# mk-logic-bt.net
KiCad netlist of a schematic drawn in EAGLE
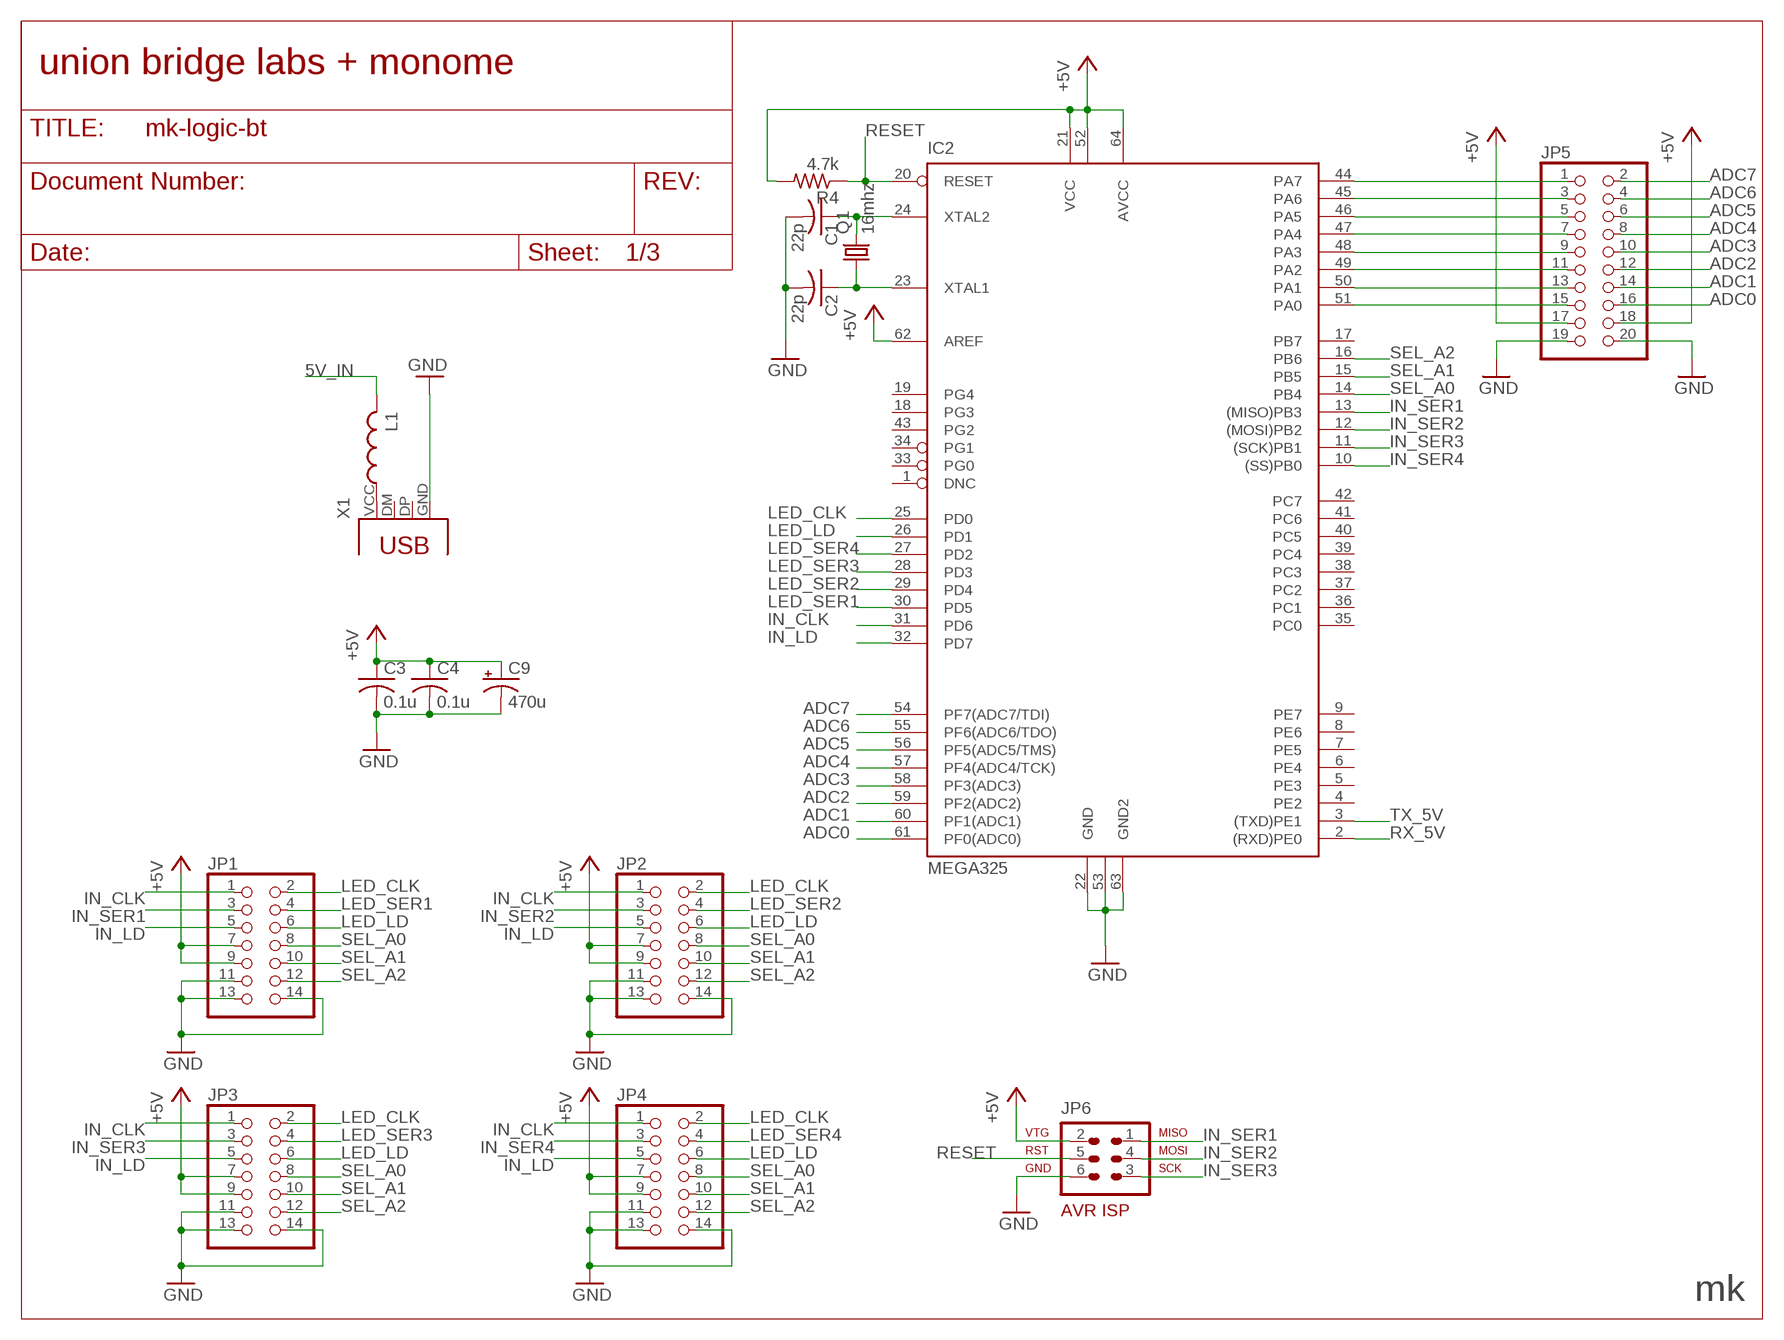
[diagram p0: schematic, sheet 1]
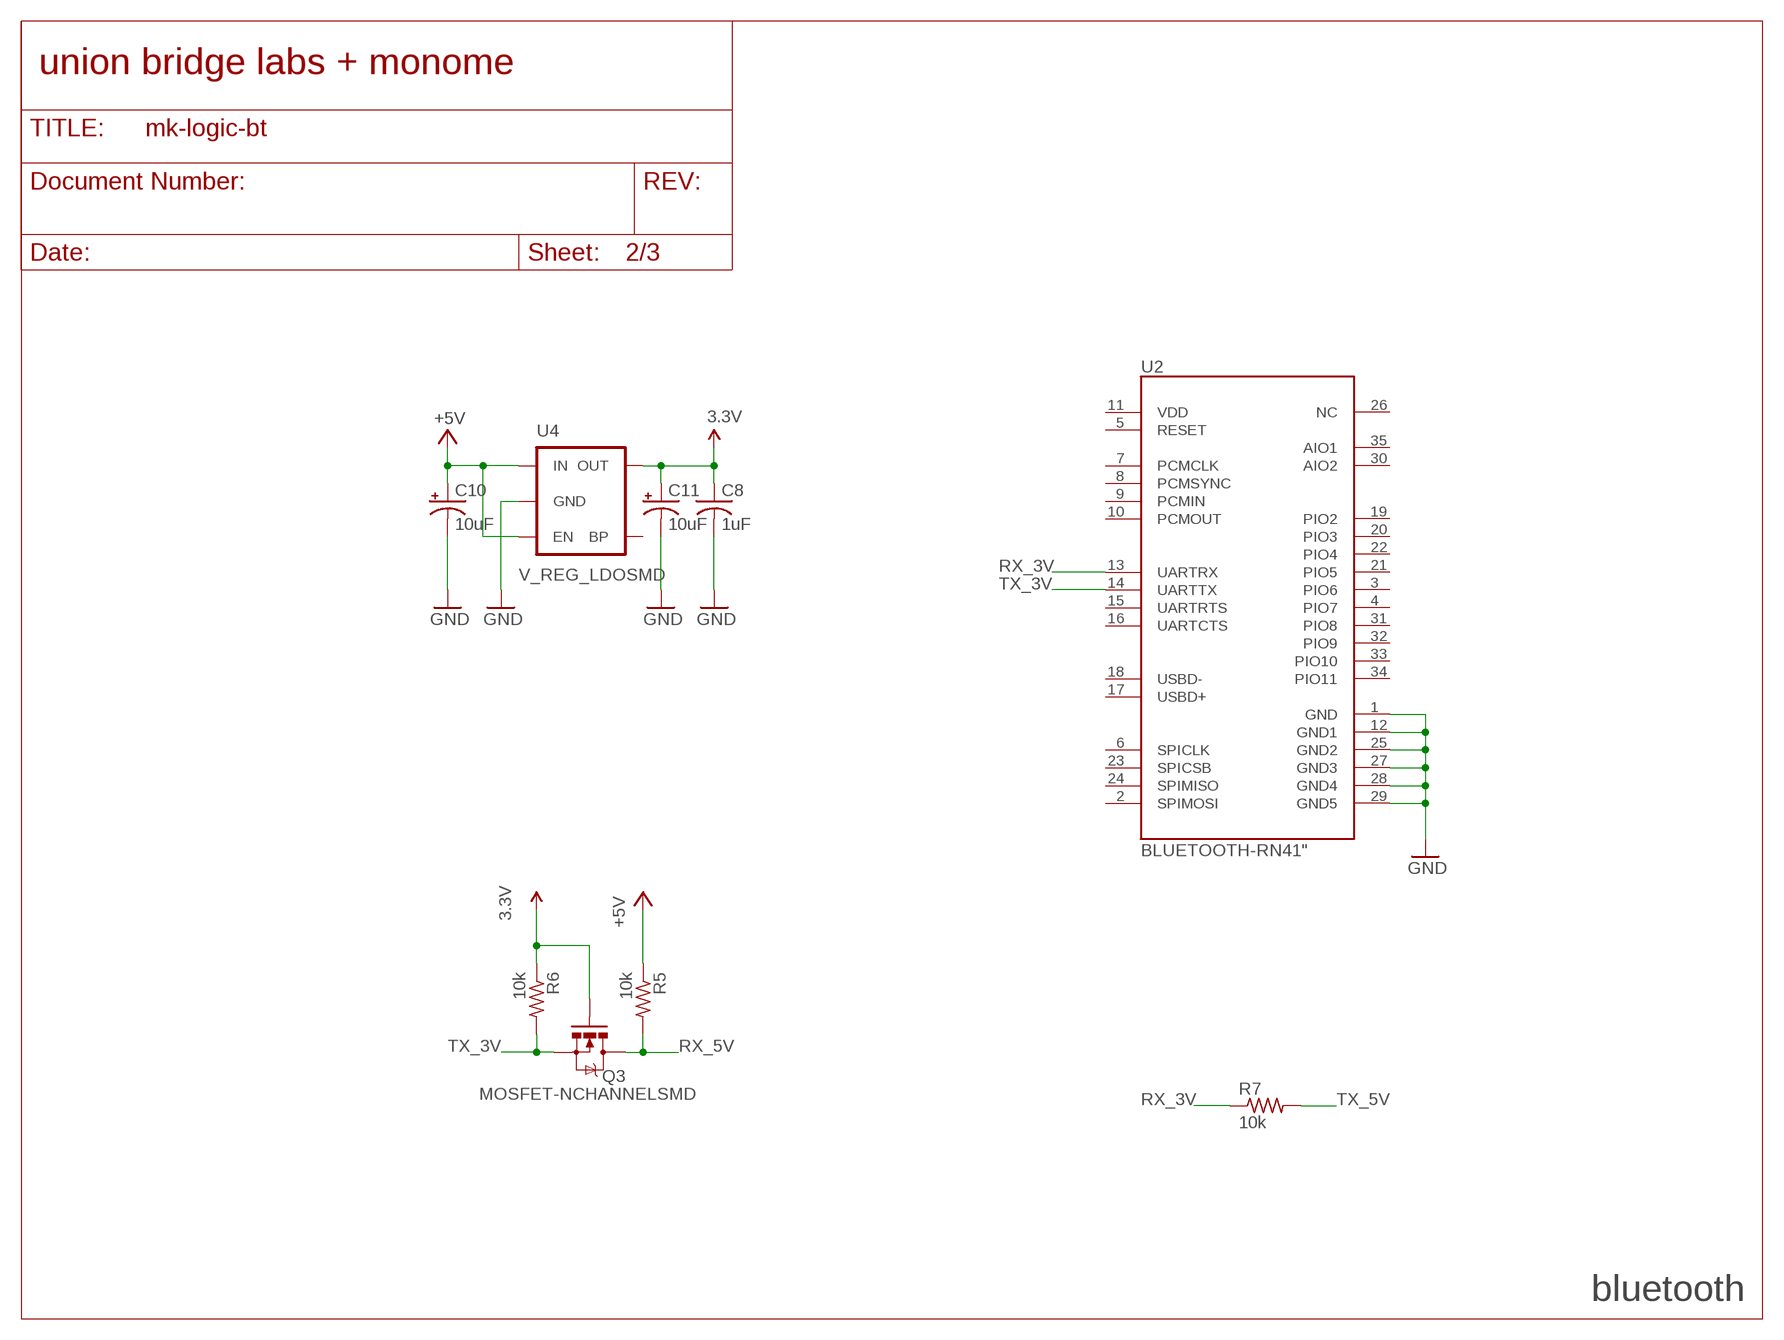
[diagram p1: schematic, sheet 2]
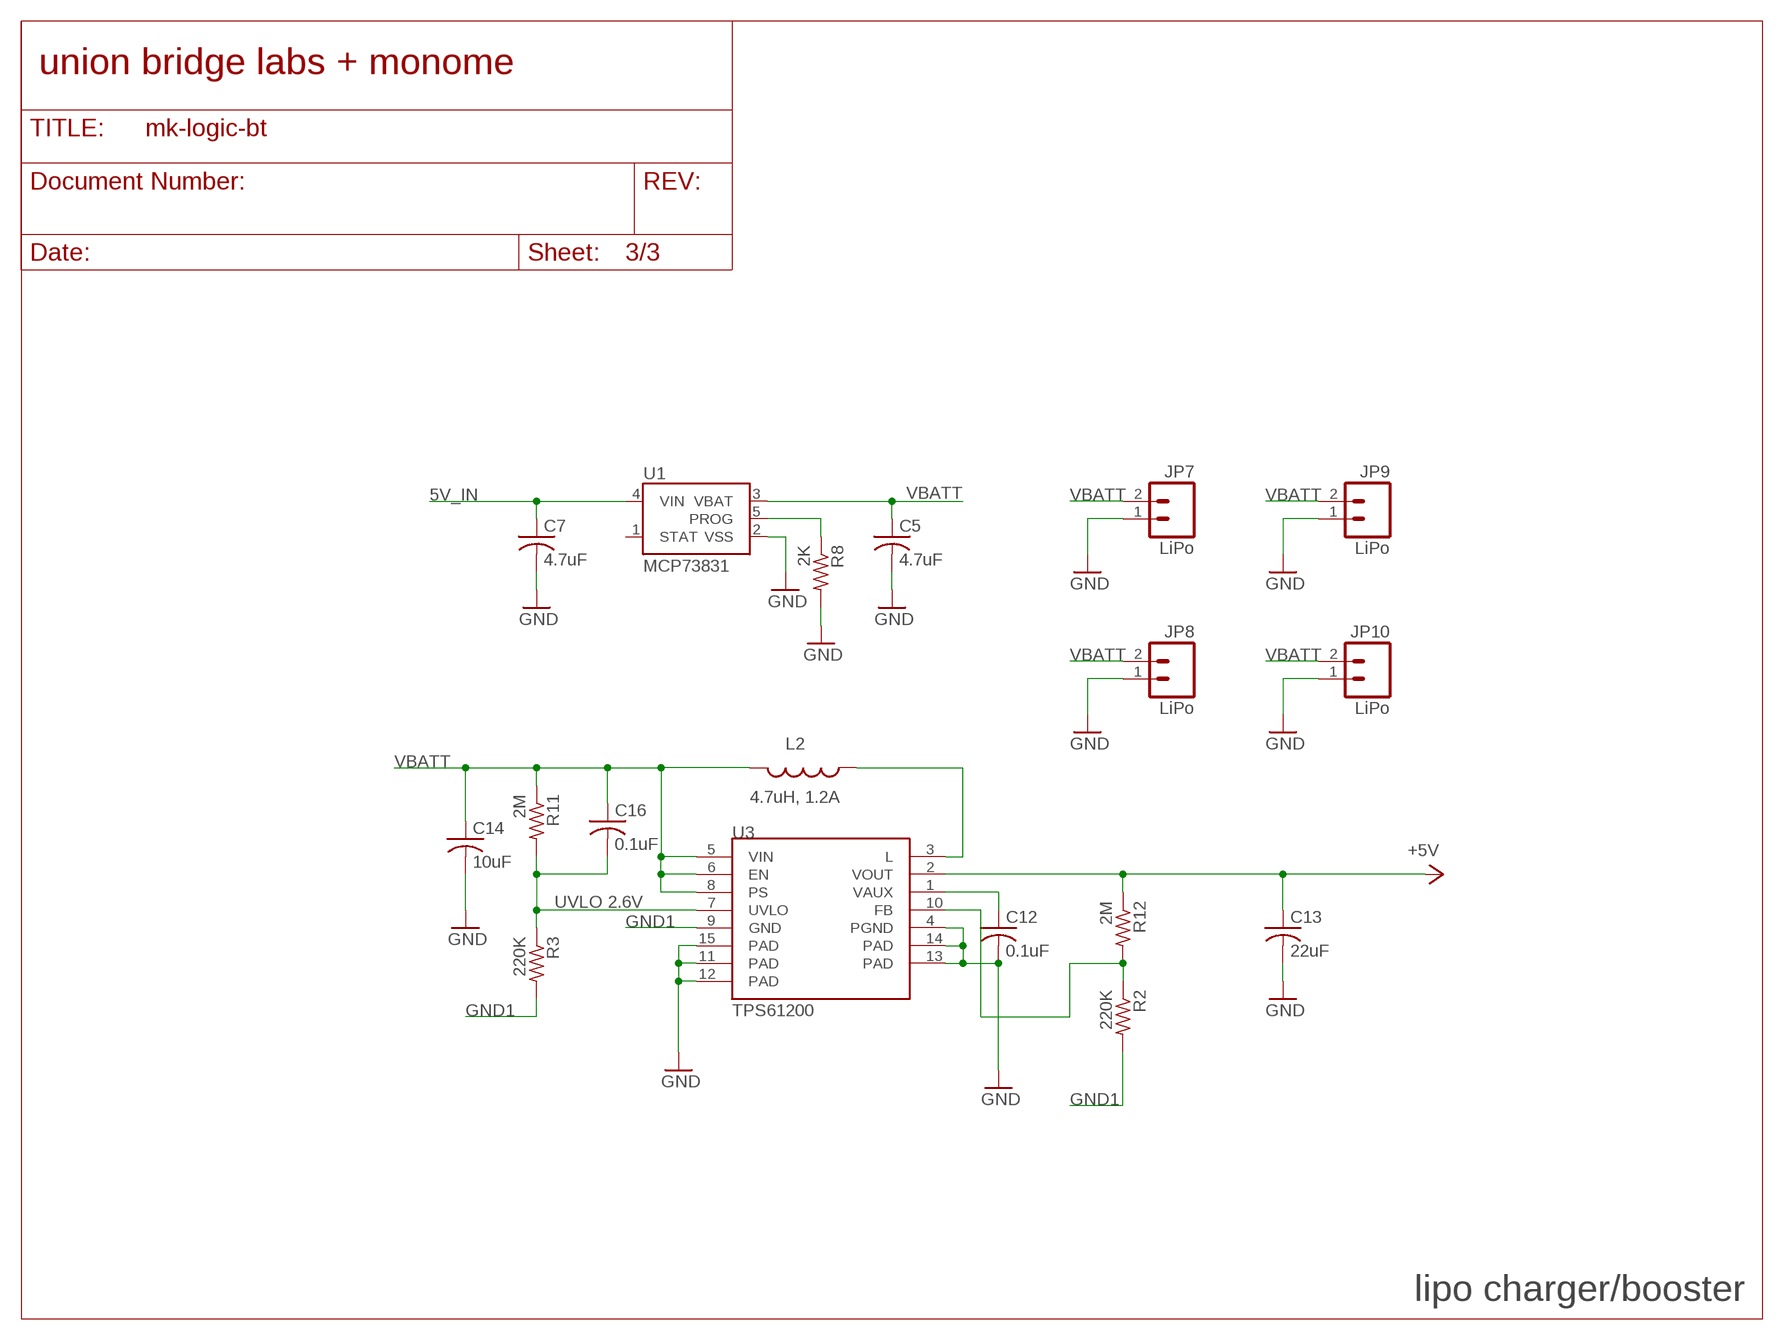
[diagram p2: schematic, sheet 3]

(export (version "E")
  (design (tool "Eeschema 10.0.6"))
  (components
    (comp (ref "C1")
      (value "22p")
      (footprint "eagle-import:C1206")
      (libsource (lib "eagle-import") (part "C-USC1206"))
    )
    (comp (ref "C2")
      (value "22p")
      (footprint "eagle-import:C1206")
      (libsource (lib "eagle-import") (part "C-USC1206"))
    )
    (comp (ref "C3")
      (value "0.1u")
      (footprint "eagle-import:C1206")
      (libsource (lib "eagle-import") (part "C-USC1206"))
    )
    (comp (ref "C4")
      (value "0.1u")
      (footprint "eagle-import:C1206")
      (libsource (lib "eagle-import") (part "C-USC1206"))
    )
    (comp (ref "C9")
      (value "470u")
      (footprint "eagle-import:PANASONIC_E")
      (libsource (lib "eagle-import") (part "CPOL-USE"))
    )
    (comp (ref "IC2")
      (value "MEGA325")
      (footprint "eagle-import:TQFP64")
      (libsource (lib "eagle-import") (part "MEGA325"))
    )
    (comp (ref "JP1")
      (value "PINHD-2X7")
      (footprint "eagle-import:2X07")
      (libsource (lib "eagle-import") (part "PINHD-2X7"))
    )
    (comp (ref "JP2")
      (value "PINHD-2X7")
      (footprint "eagle-import:2X07")
      (libsource (lib "eagle-import") (part "PINHD-2X7"))
    )
    (comp (ref "JP3")
      (value "PINHD-2X7")
      (footprint "eagle-import:2X07")
      (libsource (lib "eagle-import") (part "PINHD-2X7"))
    )
    (comp (ref "JP4")
      (value "PINHD-2X7")
      (footprint "eagle-import:2X07")
      (libsource (lib "eagle-import") (part "PINHD-2X7"))
    )
    (comp (ref "JP5")
      (value "PINHD-2X10")
      (footprint "eagle-import:2X10")
      (libsource (lib "eagle-import") (part "PINHD-2X10"))
    )
    (comp (ref "JP6")
      (value "AVR-ISP")
      (footprint "eagle-import:AVR-ISP-6")
      (libsource (lib "eagle-import") (part "AVR-ISP-6"))
    )
    (comp (ref "L1")
      (value "L-USL3216C")
      (footprint "eagle-import:L3216C")
      (libsource (lib "eagle-import") (part "L-USL3216C"))
    )
    (comp (ref "Q1")
      (value "16mhz")
      (footprint "eagle-import:HC49UP")
      (libsource (lib "eagle-import") (part "CRYTALHC49UP"))
    )
    (comp (ref "R4")
      (value "4.7k")
      (footprint "eagle-import:R1206")
      (libsource (lib "eagle-import") (part "R-US_R1206"))
    )
    (comp (ref "X1")
      (value "USB_TYPE_B")
      (footprint "eagle-import:USB_B")
      (libsource (lib "eagle-import") (part "USB_TYPE_B"))
    )
    (comp (ref "C5")
      (value "4.7uF")
      (footprint "eagle-import:C1206")
      (libsource (lib "eagle-import") (part "C-USC1206"))
    )
    (comp (ref "C7")
      (value "4.7uF")
      (footprint "eagle-import:C1206")
      (libsource (lib "eagle-import") (part "C-USC1206"))
    )
    (comp (ref "C12")
      (value "0.1uF")
      (footprint "eagle-import:C1206")
      (libsource (lib "eagle-import") (part "C-USC1206"))
    )
    (comp (ref "C13")
      (value "22uF")
      (footprint "eagle-import:C1206")
      (libsource (lib "eagle-import") (part "C-USC1206"))
    )
    (comp (ref "C14")
      (value "10uF")
      (footprint "eagle-import:C1206")
      (libsource (lib "eagle-import") (part "C-USC1206"))
    )
    (comp (ref "C16")
      (value "0.1uF")
      (footprint "eagle-import:C1206")
      (libsource (lib "eagle-import") (part "C-USC1206"))
    )
    (comp (ref "JP7")
      (value "LiPo")
      (footprint "eagle-import:JST-2-SMD")
      (libsource (lib "eagle-import") (part "M02-JST-2MM-SMT"))
    )
    (comp (ref "JP8")
      (value "LiPo")
      (footprint "eagle-import:JST-2-SMD")
      (libsource (lib "eagle-import") (part "M02-JST-2MM-SMT"))
    )
    (comp (ref "JP9")
      (value "LiPo")
      (footprint "eagle-import:JST-2-SMD")
      (libsource (lib "eagle-import") (part "M02-JST-2MM-SMT"))
    )
    (comp (ref "JP10")
      (value "LiPo")
      (footprint "eagle-import:JST-2-SMD")
      (libsource (lib "eagle-import") (part "M02-JST-2MM-SMT"))
    )
    (comp (ref "L2")
      (value "4.7uH, 1.2A")
      (footprint "eagle-import:CDRH2D09")
      (libsource (lib "eagle-import") (part "INDUCTOR."))
    )
    (comp (ref "R2")
      (value "220K")
      (footprint "eagle-import:R1206")
      (libsource (lib "eagle-import") (part "R-US_R1206"))
    )
    (comp (ref "R3")
      (value "220K")
      (footprint "eagle-import:R1206")
      (libsource (lib "eagle-import") (part "R-US_R1206"))
    )
    (comp (ref "R8")
      (value "2K")
      (footprint "eagle-import:R1206")
      (libsource (lib "eagle-import") (part "R-US_R1206"))
    )
    (comp (ref "R11")
      (value "2M")
      (footprint "eagle-import:R1206")
      (libsource (lib "eagle-import") (part "R-US_R1206"))
    )
    (comp (ref "R12")
      (value "2M")
      (footprint "eagle-import:R1206")
      (libsource (lib "eagle-import") (part "R-US_R1206"))
    )
    (comp (ref "U1")
      (value "MCP73831")
      (footprint "eagle-import:SOT23-5")
      (libsource (lib "eagle-import") (part "MCP73831"))
    )
    (comp (ref "U3")
      (value "TPS61200")
      (footprint "eagle-import:QFN-10_PAD")
      (libsource (lib "eagle-import") (part "TPS61200"))
    )
    (comp (ref "C8")
      (value "1uF")
      (footprint "eagle-import:C1206")
      (libsource (lib "eagle-import") (part "C-USC1206"))
    )
    (comp (ref "C10")
      (value "10uF")
      (footprint "eagle-import:EIA3216")
      (libsource (lib "eagle-import") (part "CAP_POL1206"))
    )
    (comp (ref "C11")
      (value "10uF")
      (footprint "eagle-import:EIA3216")
      (libsource (lib "eagle-import") (part "CAP_POL1206"))
    )
    (comp (ref "Q3")
      (value "MOSFET-NCHANNELSMD")
      (footprint "eagle-import:SOT23-3")
      (libsource (lib "eagle-import") (part "MOSFET-NCHANNELSMD"))
    )
    (comp (ref "R5")
      (value "10k")
      (footprint "eagle-import:R1206")
      (libsource (lib "eagle-import") (part "R-US_R1206"))
    )
    (comp (ref "R6")
      (value "10k")
      (footprint "eagle-import:R1206")
      (libsource (lib "eagle-import") (part "R-US_R1206"))
    )
    (comp (ref "R7")
      (value "10k")
      (footprint "eagle-import:R1206")
      (libsource (lib "eagle-import") (part "R-US_R1206"))
    )
    (comp (ref "U2")
      (value "BLUETOOTH-RN41\"")
      (footprint "eagle-import:RN41")
      (libsource (lib "eagle-import") (part "BLUETOOTH-RN41{dblquote}"))
    )
    (comp (ref "U4")
      (value "V_REG_LDOSMD")
      (footprint "eagle-import:SOT23-5")
      (libsource (lib "eagle-import") (part "V_REG_LDOSMD"))
    )
  )
  (nets
    (net (code "1") (name "+5V") (class "Default")
      (node (ref "C10") (pin "A") (pinfunction "+_A") (pintype "passive"))
      (node (ref "C13") (pin "1") (pinfunction "1_1") (pintype "passive"))
      (node (ref "C3") (pin "1") (pinfunction "1_1") (pintype "passive"))
      (node (ref "C4") (pin "1") (pinfunction "1_1") (pintype "passive"))
      (node (ref "C9") (pin "+") (pinfunction "+_+") (pintype "passive"))
      (node (ref "IC2") (pin "21") (pinfunction "VCC_21") (pintype "power_in"))
      (node (ref "IC2") (pin "52") (pinfunction "VCC1_52") (pintype "power_in"))
      (node (ref "IC2") (pin "62") (pinfunction "AREF_62") (pintype "bidirectional"))
      (node (ref "IC2") (pin "64") (pinfunction "AVCC_64") (pintype "bidirectional"))
      (node (ref "JP1") (pin "7") (pinfunction "7_7") (pintype "passive"))
      (node (ref "JP1") (pin "9") (pinfunction "9_9") (pintype "passive"))
      (node (ref "JP2") (pin "7") (pinfunction "7_7") (pintype "passive"))
      (node (ref "JP2") (pin "9") (pinfunction "9_9") (pintype "passive"))
      (node (ref "JP3") (pin "7") (pinfunction "7_7") (pintype "passive"))
      (node (ref "JP3") (pin "9") (pinfunction "9_9") (pintype "passive"))
      (node (ref "JP4") (pin "7") (pinfunction "7_7") (pintype "passive"))
      (node (ref "JP4") (pin "9") (pinfunction "9_9") (pintype "passive"))
      (node (ref "JP5") (pin "17") (pinfunction "17_17") (pintype "passive"))
      (node (ref "JP5") (pin "18") (pinfunction "18_18") (pintype "passive"))
      (node (ref "JP6") (pin "2") (pinfunction "2_2") (pintype "passive"))
      (node (ref "R12") (pin "1") (pinfunction "1_1") (pintype "passive"))
      (node (ref "R4") (pin "2") (pinfunction "2_2") (pintype "passive"))
      (node (ref "R5") (pin "1") (pinfunction "1_1") (pintype "passive"))
      (node (ref "U3") (pin "2") (pinfunction "VOUT_2") (pintype "passive"))
      (node (ref "U4") (pin "1") (pinfunction "IN_1") (pintype "input"))
      (node (ref "U4") (pin "3") (pinfunction "EN_3") (pintype "input"))
    )
    (net (code "2") (name "3.3V") (class "Default")
      (node (ref "C11") (pin "A") (pinfunction "+_A") (pintype "passive"))
      (node (ref "C8") (pin "1") (pinfunction "1_1") (pintype "passive"))
      (node (ref "Q3") (pin "1") (pinfunction "G_1") (pintype "passive"))
      (node (ref "R6") (pin "1") (pinfunction "1_1") (pintype "passive"))
      (node (ref "U4") (pin "5") (pinfunction "OUT_5") (pintype "passive"))
    )
    (net (code "3") (name "5V_IN") (class "Default")
      (node (ref "C7") (pin "1") (pinfunction "1_1") (pintype "passive"))
      (node (ref "L1") (pin "2") (pinfunction "2_2") (pintype "passive"))
      (node (ref "U1") (pin "4") (pinfunction "VIN_4") (pintype "power_in"))
    )
    (net (code "4") (name "ADC0") (class "Default")
      (node (ref "IC2") (pin "61") (pinfunction "PF0(ADC0)_61") (pintype "input"))
      (node (ref "JP5") (pin "16") (pinfunction "16_16") (pintype "passive"))
    )
    (net (code "5") (name "ADC1") (class "Default")
      (node (ref "IC2") (pin "60") (pinfunction "PF1(ADC1)_60") (pintype "input"))
      (node (ref "JP5") (pin "14") (pinfunction "14_14") (pintype "passive"))
    )
    (net (code "6") (name "ADC2") (class "Default")
      (node (ref "IC2") (pin "59") (pinfunction "PF2(ADC2)_59") (pintype "input"))
      (node (ref "JP5") (pin "12") (pinfunction "12_12") (pintype "passive"))
    )
    (net (code "7") (name "ADC3") (class "Default")
      (node (ref "IC2") (pin "58") (pinfunction "PF3(ADC3)_58") (pintype "input"))
      (node (ref "JP5") (pin "10") (pinfunction "10_10") (pintype "passive"))
    )
    (net (code "8") (name "ADC4") (class "Default")
      (node (ref "IC2") (pin "57") (pinfunction "PF4(ADC4/TCK)_57") (pintype "input"))
      (node (ref "JP5") (pin "8") (pinfunction "8_8") (pintype "passive"))
    )
    (net (code "9") (name "ADC5") (class "Default")
      (node (ref "IC2") (pin "56") (pinfunction "PF5(ADC5/TMS)_56") (pintype "input"))
      (node (ref "JP5") (pin "6") (pinfunction "6_6") (pintype "passive"))
    )
    (net (code "10") (name "ADC6") (class "Default")
      (node (ref "IC2") (pin "55") (pinfunction "PF6(ADC6/TDO)_55") (pintype "input"))
      (node (ref "JP5") (pin "4") (pinfunction "4_4") (pintype "passive"))
    )
    (net (code "11") (name "ADC7") (class "Default")
      (node (ref "IC2") (pin "54") (pinfunction "PF7(ADC7/TDI)_54") (pintype "input"))
      (node (ref "JP5") (pin "2") (pinfunction "2_2") (pintype "passive"))
    )
    (net (code "12") (name "GND") (class "Default")
      (node (ref "C1") (pin "2") (pinfunction "2_2") (pintype "passive"))
      (node (ref "C10") (pin "C") (pinfunction "-_C") (pintype "passive"))
      (node (ref "C11") (pin "C") (pinfunction "-_C") (pintype "passive"))
      (node (ref "C12") (pin "2") (pinfunction "2_2") (pintype "passive"))
      (node (ref "C13") (pin "2") (pinfunction "2_2") (pintype "passive"))
      (node (ref "C14") (pin "2") (pinfunction "2_2") (pintype "passive"))
      (node (ref "C2") (pin "2") (pinfunction "2_2") (pintype "passive"))
      (node (ref "C3") (pin "2") (pinfunction "2_2") (pintype "passive"))
      (node (ref "C4") (pin "2") (pinfunction "2_2") (pintype "passive"))
      (node (ref "C5") (pin "2") (pinfunction "2_2") (pintype "passive"))
      (node (ref "C7") (pin "2") (pinfunction "2_2") (pintype "passive"))
      (node (ref "C8") (pin "2") (pinfunction "2_2") (pintype "passive"))
      (node (ref "C9") (pin "-") (pinfunction "-_-") (pintype "passive"))
      (node (ref "IC2") (pin "22") (pinfunction "GND_22") (pintype "power_in"))
      (node (ref "IC2") (pin "53") (pinfunction "GND1_53") (pintype "power_in"))
      (node (ref "IC2") (pin "63") (pinfunction "GND2_63") (pintype "bidirectional"))
      (node (ref "JP1") (pin "11") (pinfunction "11_11") (pintype "passive"))
      (node (ref "JP1") (pin "13") (pinfunction "13_13") (pintype "passive"))
      (node (ref "JP1") (pin "14") (pinfunction "14_14") (pintype "passive"))
      (node (ref "JP10") (pin "1") (pinfunction "1_1") (pintype "passive"))
      (node (ref "JP2") (pin "11") (pinfunction "11_11") (pintype "passive"))
      (node (ref "JP2") (pin "13") (pinfunction "13_13") (pintype "passive"))
      (node (ref "JP2") (pin "14") (pinfunction "14_14") (pintype "passive"))
      (node (ref "JP3") (pin "11") (pinfunction "11_11") (pintype "passive"))
      (node (ref "JP3") (pin "13") (pinfunction "13_13") (pintype "passive"))
      (node (ref "JP3") (pin "14") (pinfunction "14_14") (pintype "passive"))
      (node (ref "JP4") (pin "11") (pinfunction "11_11") (pintype "passive"))
      (node (ref "JP4") (pin "13") (pinfunction "13_13") (pintype "passive"))
      (node (ref "JP4") (pin "14") (pinfunction "14_14") (pintype "passive"))
      (node (ref "JP5") (pin "19") (pinfunction "19_19") (pintype "passive"))
      (node (ref "JP5") (pin "20") (pinfunction "20_20") (pintype "passive"))
      (node (ref "JP6") (pin "6") (pinfunction "6_6") (pintype "passive"))
      (node (ref "JP7") (pin "1") (pinfunction "1_1") (pintype "passive"))
      (node (ref "JP8") (pin "1") (pinfunction "1_1") (pintype "passive"))
      (node (ref "JP9") (pin "1") (pinfunction "1_1") (pintype "passive"))
      (node (ref "R8") (pin "2") (pinfunction "2_2") (pintype "passive"))
      (node (ref "U1") (pin "2") (pinfunction "VSS_2") (pintype "power_in"))
      (node (ref "U2") (pin "1") (pinfunction "GND_1") (pintype "bidirectional"))
      (node (ref "U2") (pin "12") (pinfunction "GND1_12") (pintype "bidirectional"))
      (node (ref "U2") (pin "25") (pinfunction "GND2_25") (pintype "bidirectional"))
      (node (ref "U2") (pin "27") (pinfunction "GND3_27") (pintype "bidirectional"))
      (node (ref "U2") (pin "28") (pinfunction "GND4_28") (pintype "bidirectional"))
      (node (ref "U2") (pin "29") (pinfunction "GND5_29") (pintype "bidirectional"))
      (node (ref "U3") (pin "11") (pinfunction "PAD_11") (pintype "power_in"))
      (node (ref "U3") (pin "12") (pinfunction "PAD_12") (pintype "power_in"))
      (node (ref "U3") (pin "13") (pinfunction "PAD_13") (pintype "power_in"))
      (node (ref "U3") (pin "14") (pinfunction "PAD_14") (pintype "power_in"))
      (node (ref "U3") (pin "15") (pinfunction "PAD_15") (pintype "power_in"))
      (node (ref "U3") (pin "4") (pinfunction "PGND_4") (pintype "power_in"))
      (node (ref "U4") (pin "2") (pinfunction "GND_2") (pintype "input"))
      (node (ref "X1") (pin "GND") (pinfunction "GND_GND") (pintype "bidirectional"))
    )
    (net (code "13") (name "GND1") (class "Default")
      (node (ref "R2") (pin "2") (pinfunction "2_2") (pintype "passive"))
      (node (ref "R3") (pin "2") (pinfunction "2_2") (pintype "passive"))
      (node (ref "U3") (pin "9") (pinfunction "GND_9") (pintype "power_in"))
    )
    (net (code "14") (name "IN_CLK") (class "Default")
      (node (ref "IC2") (pin "31") (pinfunction "PD6_31") (pintype "bidirectional"))
      (node (ref "JP1") (pin "1") (pinfunction "1_1") (pintype "passive"))
      (node (ref "JP2") (pin "1") (pinfunction "1_1") (pintype "passive"))
      (node (ref "JP3") (pin "1") (pinfunction "1_1") (pintype "passive"))
      (node (ref "JP4") (pin "1") (pinfunction "1_1") (pintype "passive"))
    )
    (net (code "15") (name "IN_LD") (class "Default")
      (node (ref "IC2") (pin "32") (pinfunction "PD7_32") (pintype "bidirectional"))
      (node (ref "JP1") (pin "5") (pinfunction "5_5") (pintype "passive"))
      (node (ref "JP2") (pin "5") (pinfunction "5_5") (pintype "passive"))
      (node (ref "JP3") (pin "5") (pinfunction "5_5") (pintype "passive"))
      (node (ref "JP4") (pin "5") (pinfunction "5_5") (pintype "passive"))
    )
    (net (code "16") (name "IN_SER1") (class "Default")
      (node (ref "IC2") (pin "13") (pinfunction "(MISO)PB3_13") (pintype "bidirectional"))
      (node (ref "JP1") (pin "3") (pinfunction "3_3") (pintype "passive"))
      (node (ref "JP6") (pin "1") (pinfunction "1_1") (pintype "passive"))
    )
    (net (code "17") (name "IN_SER2") (class "Default")
      (node (ref "IC2") (pin "12") (pinfunction "(MOSI)PB2_12") (pintype "bidirectional"))
      (node (ref "JP2") (pin "3") (pinfunction "3_3") (pintype "passive"))
      (node (ref "JP6") (pin "4") (pinfunction "4_4") (pintype "passive"))
    )
    (net (code "18") (name "IN_SER3") (class "Default")
      (node (ref "IC2") (pin "11") (pinfunction "(SCK)PB1_11") (pintype "bidirectional"))
      (node (ref "JP3") (pin "3") (pinfunction "3_3") (pintype "passive"))
      (node (ref "JP6") (pin "3") (pinfunction "3_3") (pintype "passive"))
    )
    (net (code "19") (name "IN_SER4") (class "Default")
      (node (ref "IC2") (pin "10") (pinfunction "(SS)PB0_10") (pintype "bidirectional"))
      (node (ref "JP4") (pin "3") (pinfunction "3_3") (pintype "passive"))
    )
    (net (code "20") (name "LED_CLK") (class "Default")
      (node (ref "IC2") (pin "25") (pinfunction "PD0_25") (pintype "bidirectional"))
      (node (ref "JP1") (pin "2") (pinfunction "2_2") (pintype "passive"))
      (node (ref "JP2") (pin "2") (pinfunction "2_2") (pintype "passive"))
      (node (ref "JP3") (pin "2") (pinfunction "2_2") (pintype "passive"))
      (node (ref "JP4") (pin "2") (pinfunction "2_2") (pintype "passive"))
    )
    (net (code "21") (name "LED_LD") (class "Default")
      (node (ref "IC2") (pin "26") (pinfunction "PD1_26") (pintype "bidirectional"))
      (node (ref "JP1") (pin "6") (pinfunction "6_6") (pintype "passive"))
      (node (ref "JP2") (pin "6") (pinfunction "6_6") (pintype "passive"))
      (node (ref "JP3") (pin "6") (pinfunction "6_6") (pintype "passive"))
      (node (ref "JP4") (pin "6") (pinfunction "6_6") (pintype "passive"))
    )
    (net (code "22") (name "LED_SER1") (class "Default")
      (node (ref "IC2") (pin "30") (pinfunction "PD5_30") (pintype "bidirectional"))
      (node (ref "JP1") (pin "4") (pinfunction "4_4") (pintype "passive"))
    )
    (net (code "23") (name "LED_SER2") (class "Default")
      (node (ref "IC2") (pin "29") (pinfunction "PD4_29") (pintype "bidirectional"))
      (node (ref "JP2") (pin "4") (pinfunction "4_4") (pintype "passive"))
    )
    (net (code "24") (name "LED_SER3") (class "Default")
      (node (ref "IC2") (pin "28") (pinfunction "PD3_28") (pintype "bidirectional"))
      (node (ref "JP3") (pin "4") (pinfunction "4_4") (pintype "passive"))
    )
    (net (code "25") (name "LED_SER4") (class "Default")
      (node (ref "IC2") (pin "27") (pinfunction "PD2_27") (pintype "bidirectional"))
      (node (ref "JP4") (pin "4") (pinfunction "4_4") (pintype "passive"))
    )
    (net (code "26") (name "Net-(IC2-PA0)") (class "Default")
      (node (ref "IC2") (pin "51") (pinfunction "PA0_51") (pintype "bidirectional"))
      (node (ref "JP5") (pin "15") (pinfunction "15_15") (pintype "passive"))
    )
    (net (code "27") (name "Net-(IC2-PA1)") (class "Default")
      (node (ref "IC2") (pin "50") (pinfunction "PA1_50") (pintype "bidirectional"))
      (node (ref "JP5") (pin "13") (pinfunction "13_13") (pintype "passive"))
    )
    (net (code "28") (name "Net-(IC2-PA2)") (class "Default")
      (node (ref "IC2") (pin "49") (pinfunction "PA2_49") (pintype "bidirectional"))
      (node (ref "JP5") (pin "11") (pinfunction "11_11") (pintype "passive"))
    )
    (net (code "29") (name "Net-(IC2-PA3)") (class "Default")
      (node (ref "IC2") (pin "48") (pinfunction "PA3_48") (pintype "bidirectional"))
      (node (ref "JP5") (pin "9") (pinfunction "9_9") (pintype "passive"))
    )
    (net (code "30") (name "Net-(IC2-PA4)") (class "Default")
      (node (ref "IC2") (pin "47") (pinfunction "PA4_47") (pintype "bidirectional"))
      (node (ref "JP5") (pin "7") (pinfunction "7_7") (pintype "passive"))
    )
    (net (code "31") (name "Net-(IC2-PA5)") (class "Default")
      (node (ref "IC2") (pin "46") (pinfunction "PA5_46") (pintype "bidirectional"))
      (node (ref "JP5") (pin "5") (pinfunction "5_5") (pintype "passive"))
    )
    (net (code "32") (name "Net-(IC2-PA6)") (class "Default")
      (node (ref "IC2") (pin "45") (pinfunction "PA6_45") (pintype "bidirectional"))
      (node (ref "JP5") (pin "3") (pinfunction "3_3") (pintype "passive"))
    )
    (net (code "33") (name "Net-(IC2-PA7)") (class "Default")
      (node (ref "IC2") (pin "44") (pinfunction "PA7_44") (pintype "bidirectional"))
      (node (ref "JP5") (pin "1") (pinfunction "1_1") (pintype "passive"))
    )
    (net (code "34") (name "Net-(IC2-XTAL1)") (class "Default")
      (node (ref "C2") (pin "1") (pinfunction "1_1") (pintype "passive"))
      (node (ref "IC2") (pin "23") (pinfunction "XTAL1_23") (pintype "bidirectional"))
      (node (ref "Q1") (pin "1") (pinfunction "1_1") (pintype "passive"))
    )
    (net (code "35") (name "Net-(IC2-XTAL2)") (class "Default")
      (node (ref "C1") (pin "1") (pinfunction "1_1") (pintype "passive"))
      (node (ref "IC2") (pin "24") (pinfunction "XTAL2_24") (pintype "bidirectional"))
      (node (ref "Q1") (pin "2") (pinfunction "2_2") (pintype "passive"))
    )
    (net (code "36") (name "Net-(L1-Pad1)") (class "Default")
      (node (ref "L1") (pin "1") (pinfunction "1_1") (pintype "passive"))
      (node (ref "X1") (pin "VCC") (pinfunction "VCC_VCC") (pintype "bidirectional"))
    )
    (net (code "37") (name "Net-(L2-1)") (class "Default")
      (node (ref "L2") (pin "P$1") (pinfunction "1_P$1") (pintype "passive"))
      (node (ref "U3") (pin "3") (pinfunction "L_3") (pintype "passive"))
    )
    (net (code "38") (name "Net-(U1-PROG)") (class "Default")
      (node (ref "R8") (pin "1") (pinfunction "1_1") (pintype "passive"))
      (node (ref "U1") (pin "5") (pinfunction "PROG_5") (pintype "input"))
    )
    (net (code "39") (name "Net-(U3-FB)") (class "Default")
      (node (ref "R12") (pin "2") (pinfunction "2_2") (pintype "passive"))
      (node (ref "R2") (pin "1") (pinfunction "1_1") (pintype "passive"))
      (node (ref "U3") (pin "10") (pinfunction "FB_10") (pintype "passive"))
    )
    (net (code "40") (name "Net-(U3-UVLO)") (class "Default")
      (node (ref "C16") (pin "2") (pinfunction "2_2") (pintype "passive"))
      (node (ref "R11") (pin "2") (pinfunction "2_2") (pintype "passive"))
      (node (ref "R3") (pin "1") (pinfunction "1_1") (pintype "passive"))
      (node (ref "U3") (pin "7") (pinfunction "UVLO_7") (pintype "passive"))
    )
    (net (code "41") (name "Net-(U3-VAUX)") (class "Default")
      (node (ref "C12") (pin "1") (pinfunction "1_1") (pintype "passive"))
      (node (ref "U3") (pin "1") (pinfunction "VAUX_1") (pintype "passive"))
    )
    (net (code "42") (name "RESET") (class "Default")
      (node (ref "IC2") (pin "20") (pinfunction "RESET_20") (pintype "input"))
      (node (ref "JP6") (pin "5") (pinfunction "5_5") (pintype "passive"))
      (node (ref "R4") (pin "1") (pinfunction "1_1") (pintype "passive"))
    )
    (net (code "43") (name "RX_3V") (class "Default")
      (node (ref "R7") (pin "1") (pinfunction "1_1") (pintype "passive"))
      (node (ref "U2") (pin "13") (pinfunction "UARTRX_13") (pintype "bidirectional"))
    )
    (net (code "44") (name "RX_5V") (class "Default")
      (node (ref "IC2") (pin "2") (pinfunction "(RXD)PE0_2") (pintype "bidirectional"))
      (node (ref "Q3") (pin "3") (pinfunction "D_3") (pintype "passive"))
      (node (ref "R5") (pin "2") (pinfunction "2_2") (pintype "passive"))
    )
    (net (code "45") (name "SEL_A0") (class "Default")
      (node (ref "IC2") (pin "14") (pinfunction "PB4_14") (pintype "bidirectional"))
      (node (ref "JP1") (pin "8") (pinfunction "8_8") (pintype "passive"))
      (node (ref "JP2") (pin "8") (pinfunction "8_8") (pintype "passive"))
      (node (ref "JP3") (pin "8") (pinfunction "8_8") (pintype "passive"))
      (node (ref "JP4") (pin "8") (pinfunction "8_8") (pintype "passive"))
    )
    (net (code "46") (name "SEL_A1") (class "Default")
      (node (ref "IC2") (pin "15") (pinfunction "PB5_15") (pintype "bidirectional"))
      (node (ref "JP1") (pin "10") (pinfunction "10_10") (pintype "passive"))
      (node (ref "JP2") (pin "10") (pinfunction "10_10") (pintype "passive"))
      (node (ref "JP3") (pin "10") (pinfunction "10_10") (pintype "passive"))
      (node (ref "JP4") (pin "10") (pinfunction "10_10") (pintype "passive"))
    )
    (net (code "47") (name "SEL_A2") (class "Default")
      (node (ref "IC2") (pin "16") (pinfunction "PB6_16") (pintype "bidirectional"))
      (node (ref "JP1") (pin "12") (pinfunction "12_12") (pintype "passive"))
      (node (ref "JP2") (pin "12") (pinfunction "12_12") (pintype "passive"))
      (node (ref "JP3") (pin "12") (pinfunction "12_12") (pintype "passive"))
      (node (ref "JP4") (pin "12") (pinfunction "12_12") (pintype "passive"))
    )
    (net (code "48") (name "TX_3V") (class "Default")
      (node (ref "Q3") (pin "2") (pinfunction "S_2") (pintype "passive"))
      (node (ref "R6") (pin "2") (pinfunction "2_2") (pintype "passive"))
      (node (ref "U2") (pin "14") (pinfunction "UARTTX_14") (pintype "bidirectional"))
    )
    (net (code "49") (name "TX_5V") (class "Default")
      (node (ref "IC2") (pin "3") (pinfunction "(TXD)PE1_3") (pintype "bidirectional"))
      (node (ref "R7") (pin "2") (pinfunction "2_2") (pintype "passive"))
    )
    (net (code "50") (name "VBATT") (class "Default")
      (node (ref "C14") (pin "1") (pinfunction "1_1") (pintype "passive"))
      (node (ref "C16") (pin "1") (pinfunction "1_1") (pintype "passive"))
      (node (ref "C5") (pin "1") (pinfunction "1_1") (pintype "passive"))
      (node (ref "JP10") (pin "2") (pinfunction "2_2") (pintype "passive"))
      (node (ref "JP7") (pin "2") (pinfunction "2_2") (pintype "passive"))
      (node (ref "JP8") (pin "2") (pinfunction "2_2") (pintype "passive"))
      (node (ref "JP9") (pin "2") (pinfunction "2_2") (pintype "passive"))
      (node (ref "L2") (pin "P$2") (pinfunction "2_P$2") (pintype "passive"))
      (node (ref "R11") (pin "1") (pinfunction "1_1") (pintype "passive"))
      (node (ref "U1") (pin "3") (pinfunction "VBAT_3") (pintype "power_in"))
      (node (ref "U3") (pin "5") (pinfunction "VIN_5") (pintype "power_in"))
      (node (ref "U3") (pin "6") (pinfunction "EN_6") (pintype "input"))
      (node (ref "U3") (pin "8") (pinfunction "PS_8") (pintype "input"))
    )
    (net (code "51") (name "unconnected-(IC2-DNC-Pad1)") (class "Default")
      (node (ref "IC2") (pin "1") (pinfunction "DNC_1") (pintype "input"))
    )
    (net (code "52") (name "unconnected-(IC2-PB7-Pad17)") (class "Default")
      (node (ref "IC2") (pin "17") (pinfunction "PB7_17") (pintype "bidirectional"))
    )
    (net (code "53") (name "unconnected-(IC2-PC0-Pad35)") (class "Default")
      (node (ref "IC2") (pin "35") (pinfunction "PC0_35") (pintype "output"))
    )
    (net (code "54") (name "unconnected-(IC2-PC1-Pad36)") (class "Default")
      (node (ref "IC2") (pin "36") (pinfunction "PC1_36") (pintype "output"))
    )
    (net (code "55") (name "unconnected-(IC2-PC2-Pad37)") (class "Default")
      (node (ref "IC2") (pin "37") (pinfunction "PC2_37") (pintype "output"))
    )
    (net (code "56") (name "unconnected-(IC2-PC3-Pad38)") (class "Default")
      (node (ref "IC2") (pin "38") (pinfunction "PC3_38") (pintype "output"))
    )
    (net (code "57") (name "unconnected-(IC2-PC4-Pad39)") (class "Default")
      (node (ref "IC2") (pin "39") (pinfunction "PC4_39") (pintype "output"))
    )
    (net (code "58") (name "unconnected-(IC2-PC5-Pad40)") (class "Default")
      (node (ref "IC2") (pin "40") (pinfunction "PC5_40") (pintype "output"))
    )
    (net (code "59") (name "unconnected-(IC2-PC6-Pad41)") (class "Default")
      (node (ref "IC2") (pin "41") (pinfunction "PC6_41") (pintype "output"))
    )
    (net (code "60") (name "unconnected-(IC2-PC7-Pad42)") (class "Default")
      (node (ref "IC2") (pin "42") (pinfunction "PC7_42") (pintype "output"))
    )
    (net (code "61") (name "unconnected-(IC2-PE2-Pad4)") (class "Default")
      (node (ref "IC2") (pin "4") (pinfunction "PE2_4") (pintype "bidirectional"))
    )
    (net (code "62") (name "unconnected-(IC2-PE3-Pad5)") (class "Default")
      (node (ref "IC2") (pin "5") (pinfunction "PE3_5") (pintype "bidirectional"))
    )
    (net (code "63") (name "unconnected-(IC2-PE4-Pad6)") (class "Default")
      (node (ref "IC2") (pin "6") (pinfunction "PE4_6") (pintype "bidirectional"))
    )
    (net (code "64") (name "unconnected-(IC2-PE5-Pad7)") (class "Default")
      (node (ref "IC2") (pin "7") (pinfunction "PE5_7") (pintype "bidirectional"))
    )
    (net (code "65") (name "unconnected-(IC2-PE6-Pad8)") (class "Default")
      (node (ref "IC2") (pin "8") (pinfunction "PE6_8") (pintype "bidirectional"))
    )
    (net (code "66") (name "unconnected-(IC2-PE7-Pad9)") (class "Default")
      (node (ref "IC2") (pin "9") (pinfunction "PE7_9") (pintype "bidirectional"))
    )
    (net (code "67") (name "unconnected-(IC2-PG0-Pad33)") (class "Default")
      (node (ref "IC2") (pin "33") (pinfunction "PG0_33") (pintype "bidirectional"))
    )
    (net (code "68") (name "unconnected-(IC2-PG1-Pad34)") (class "Default")
      (node (ref "IC2") (pin "34") (pinfunction "PG1_34") (pintype "bidirectional"))
    )
    (net (code "69") (name "unconnected-(IC2-PG2-Pad43)") (class "Default")
      (node (ref "IC2") (pin "43") (pinfunction "PG2_43") (pintype "bidirectional"))
    )
    (net (code "70") (name "unconnected-(IC2-PG3-Pad18)") (class "Default")
      (node (ref "IC2") (pin "18") (pinfunction "PG3_18") (pintype "bidirectional"))
    )
    (net (code "71") (name "unconnected-(IC2-PG4-Pad19)") (class "Default")
      (node (ref "IC2") (pin "19") (pinfunction "PG4_19") (pintype "bidirectional"))
    )
    (net (code "72") (name "unconnected-(U1-STAT-Pad1)") (class "Default")
      (node (ref "U1") (pin "1") (pinfunction "STAT_1") (pintype "output"))
    )
    (net (code "73") (name "unconnected-(U2-AIO1-Pad35)") (class "Default")
      (node (ref "U2") (pin "35") (pinfunction "AIO1_35") (pintype "bidirectional"))
    )
    (net (code "74") (name "unconnected-(U2-AIO2-Pad30)") (class "Default")
      (node (ref "U2") (pin "30") (pinfunction "AIO2_30") (pintype "bidirectional"))
    )
    (net (code "75") (name "unconnected-(U2-NC-Pad26)") (class "Default")
      (node (ref "U2") (pin "26") (pinfunction "NC_26") (pintype "bidirectional"))
    )
    (net (code "76") (name "unconnected-(U2-PCMCLK-Pad7)") (class "Default")
      (node (ref "U2") (pin "7") (pinfunction "PCMCLK_7") (pintype "bidirectional"))
    )
    (net (code "77") (name "unconnected-(U2-PCMIN-Pad9)") (class "Default")
      (node (ref "U2") (pin "9") (pinfunction "PCMIN_9") (pintype "bidirectional"))
    )
    (net (code "78") (name "unconnected-(U2-PCMOUT-Pad10)") (class "Default")
      (node (ref "U2") (pin "10") (pinfunction "PCMOUT_10") (pintype "bidirectional"))
    )
    (net (code "79") (name "unconnected-(U2-PCMSYNC-Pad8)") (class "Default")
      (node (ref "U2") (pin "8") (pinfunction "PCMSYNC_8") (pintype "bidirectional"))
    )
    (net (code "80") (name "unconnected-(U2-PIO2-Pad19)") (class "Default")
      (node (ref "U2") (pin "19") (pinfunction "PIO2_19") (pintype "bidirectional"))
    )
    (net (code "81") (name "unconnected-(U2-PIO3-Pad20)") (class "Default")
      (node (ref "U2") (pin "20") (pinfunction "PIO3_20") (pintype "bidirectional"))
    )
    (net (code "82") (name "unconnected-(U2-PIO4-Pad22)") (class "Default")
      (node (ref "U2") (pin "22") (pinfunction "PIO4_22") (pintype "bidirectional"))
    )
    (net (code "83") (name "unconnected-(U2-PIO5-Pad21)") (class "Default")
      (node (ref "U2") (pin "21") (pinfunction "PIO5_21") (pintype "bidirectional"))
    )
    (net (code "84") (name "unconnected-(U2-PIO6-Pad3)") (class "Default")
      (node (ref "U2") (pin "3") (pinfunction "PIO6_3") (pintype "bidirectional"))
    )
    (net (code "85") (name "unconnected-(U2-PIO7-Pad4)") (class "Default")
      (node (ref "U2") (pin "4") (pinfunction "PIO7_4") (pintype "bidirectional"))
    )
    (net (code "86") (name "unconnected-(U2-PIO8-Pad31)") (class "Default")
      (node (ref "U2") (pin "31") (pinfunction "PIO8_31") (pintype "bidirectional"))
    )
    (net (code "87") (name "unconnected-(U2-PIO9-Pad32)") (class "Default")
      (node (ref "U2") (pin "32") (pinfunction "PIO9_32") (pintype "bidirectional"))
    )
    (net (code "88") (name "unconnected-(U2-PIO10-Pad33)") (class "Default")
      (node (ref "U2") (pin "33") (pinfunction "PIO10_33") (pintype "bidirectional"))
    )
    (net (code "89") (name "unconnected-(U2-PIO11-Pad34)") (class "Default")
      (node (ref "U2") (pin "34") (pinfunction "PIO11_34") (pintype "bidirectional"))
    )
    (net (code "90") (name "unconnected-(U2-RESET-Pad5)") (class "Default")
      (node (ref "U2") (pin "5") (pinfunction "RESET_5") (pintype "bidirectional"))
    )
    (net (code "91") (name "unconnected-(U2-SPICLK-Pad6)") (class "Default")
      (node (ref "U2") (pin "6") (pinfunction "SPICLK_6") (pintype "bidirectional"))
    )
    (net (code "92") (name "unconnected-(U2-SPICSB-Pad23)") (class "Default")
      (node (ref "U2") (pin "23") (pinfunction "SPICSB_23") (pintype "bidirectional"))
    )
    (net (code "93") (name "unconnected-(U2-SPIMISO-Pad24)") (class "Default")
      (node (ref "U2") (pin "24") (pinfunction "SPIMISO_24") (pintype "bidirectional"))
    )
    (net (code "94") (name "unconnected-(U2-SPIMOSI-Pad2)") (class "Default")
      (node (ref "U2") (pin "2") (pinfunction "SPIMOSI_2") (pintype "bidirectional"))
    )
    (net (code "95") (name "unconnected-(U2-UARTCTS-Pad16)") (class "Default")
      (node (ref "U2") (pin "16") (pinfunction "UARTCTS_16") (pintype "bidirectional"))
    )
    (net (code "96") (name "unconnected-(U2-UARTRTS-Pad15)") (class "Default")
      (node (ref "U2") (pin "15") (pinfunction "UARTRTS_15") (pintype "bidirectional"))
    )
    (net (code "97") (name "unconnected-(U2-USBD+-Pad17)") (class "Default")
      (node (ref "U2") (pin "17") (pinfunction "USBD+_17") (pintype "bidirectional"))
    )
    (net (code "98") (name "unconnected-(U2-USBD--Pad18)") (class "Default")
      (node (ref "U2") (pin "18") (pinfunction "USBD-_18") (pintype "bidirectional"))
    )
    (net (code "99") (name "unconnected-(U2-VDD-Pad11)") (class "Default")
      (node (ref "U2") (pin "11") (pinfunction "VDD_11") (pintype "bidirectional"))
    )
    (net (code "100") (name "unconnected-(U4-BP-Pad4)") (class "Default")
      (node (ref "U4") (pin "4") (pinfunction "BP_4") (pintype "input"))
    )
    (net (code "101") (name "unconnected-(X1-USBDM-PadDM)") (class "Default")
      (node (ref "X1") (pin "DM") (pinfunction "USBDM_DM") (pintype "bidirectional"))
    )
    (net (code "102") (name "unconnected-(X1-USBDP-PadDP)") (class "Default")
      (node (ref "X1") (pin "DP") (pinfunction "USBDP_DP") (pintype "bidirectional"))
    )
  )
)
